# cat24.net
KiCad netlist of a schematic drawn in EAGLE
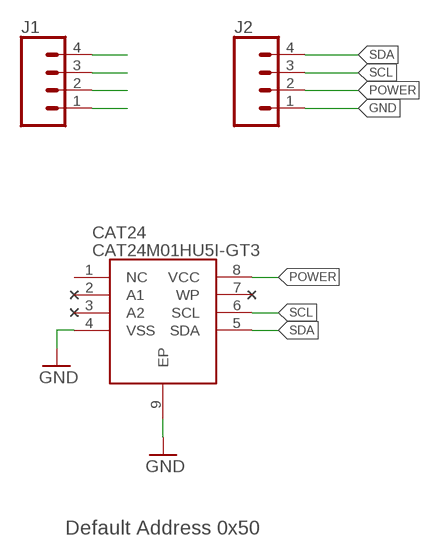
[diagram p0: schematic, sheet 1]

(export (version "E")
  (design (tool "Eeschema 10.0.6"))
  (components
    (comp (ref "CAT24")
      (value "CAT24M01HU5I-GT3")
      (footprint "eagle-import:SON50P300X200X55-9N")
      (fields
        (field (name "MOUSER_PART_NUMBER") "863-CAT24M01HU5I-GT3")
        (field (name "RS_PART_NUMBER") "7814831P")
      )
      (libsource (lib "eagle-import") (part "CAT24M01HU5I-GT3"))
    )
    (comp (ref "J1")
      (value "CONN_041X04_NO_SILK")
      (footprint "eagle-import:1X04_NO_SILK")
      (libsource (lib "eagle-import") (part "CONN_041X04_NO_SILK"))
    )
    (comp (ref "J2")
      (value "CONN_041X04_NO_SILK")
      (footprint "eagle-import:1X04_NO_SILK")
      (libsource (lib "eagle-import") (part "CONN_041X04_NO_SILK"))
    )
  )
  (nets
    (net (code "1") (name "GND") (class "Default")
      (node (ref "CAT24") (pin "4") (pinfunction "VSS_4") (pintype "power_in"))
      (node (ref "CAT24") (pin "9") (pinfunction "EP_9") (pintype "bidirectional"))
      (node (ref "J2") (pin "1") (pinfunction "1_1") (pintype "passive"))
    )
    (net (code "2") (name "POWER") (class "Default")
      (node (ref "CAT24") (pin "8") (pinfunction "VCC_8") (pintype "power_in"))
      (node (ref "J2") (pin "2") (pinfunction "2_2") (pintype "passive"))
    )
    (net (code "3") (name "SCL") (class "Default")
      (node (ref "CAT24") (pin "6") (pinfunction "SCL_6") (pintype "bidirectional"))
      (node (ref "J2") (pin "3") (pinfunction "3_3") (pintype "passive"))
    )
    (net (code "4") (name "SDA") (class "Default")
      (node (ref "CAT24") (pin "5") (pinfunction "SDA_5") (pintype "bidirectional"))
      (node (ref "J2") (pin "4") (pinfunction "4_4") (pintype "passive"))
    )
    (net (code "5") (name "unconnected-(CAT24-A1-Pad2)") (class "Default")
      (node (ref "CAT24") (pin "2") (pinfunction "A1_2") (pintype "bidirectional"))
    )
    (net (code "6") (name "unconnected-(CAT24-A2-Pad3)") (class "Default")
      (node (ref "CAT24") (pin "3") (pinfunction "A2_3") (pintype "bidirectional"))
    )
    (net (code "7") (name "unconnected-(CAT24-NC-Pad1)") (class "Default")
      (node (ref "CAT24") (pin "1") (pinfunction "NC_1") (pintype "no_connect"))
    )
    (net (code "8") (name "unconnected-(CAT24-WP-Pad7)") (class "Default")
      (node (ref "CAT24") (pin "7") (pinfunction "WP_7") (pintype "bidirectional"))
    )
    (net (code "9") (name "unconnected-(J1-Pad1)") (class "Default")
      (node (ref "J1") (pin "1") (pinfunction "1_1") (pintype "passive"))
    )
    (net (code "10") (name "unconnected-(J1-Pad2)") (class "Default")
      (node (ref "J1") (pin "2") (pinfunction "2_2") (pintype "passive"))
    )
    (net (code "11") (name "unconnected-(J1-Pad3)") (class "Default")
      (node (ref "J1") (pin "3") (pinfunction "3_3") (pintype "passive"))
    )
    (net (code "12") (name "unconnected-(J1-Pad4)") (class "Default")
      (node (ref "J1") (pin "4") (pinfunction "4_4") (pintype "passive"))
    )
  )
)
